# rc2014_8254.net
KiCad netlist of a schematic drawn in EAGLE
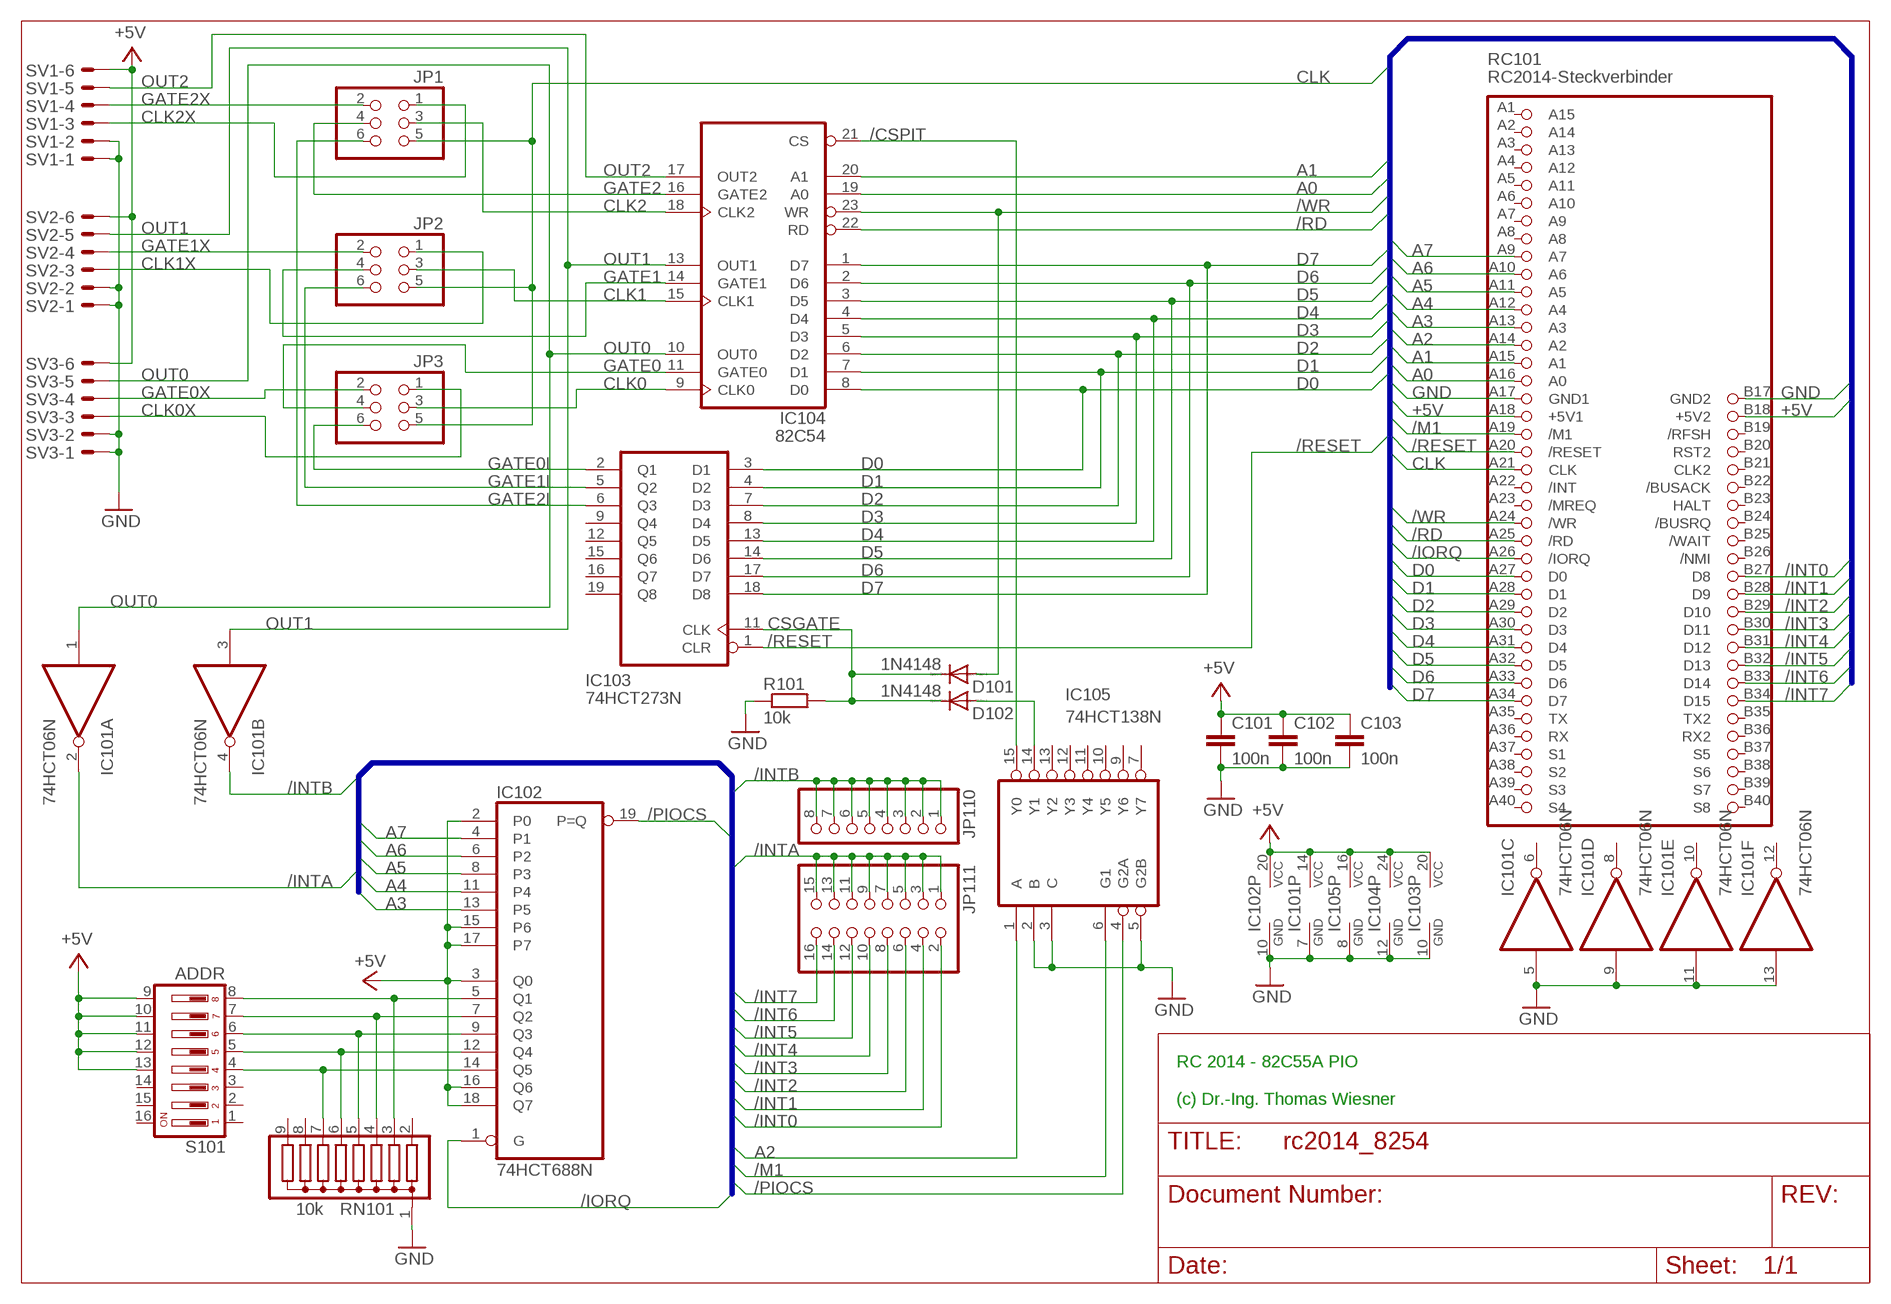
[diagram p0: schematic, sheet 1]

(export (version "E")
  (design (tool "Eeschema 10.0.6"))
  (components
    (comp (ref "C101")
      (value "100n")
      (footprint "eagle-import:C025-025X050")
      (libsource (lib "eagle-import") (part "C-EU025-025X050"))
    )
    (comp (ref "C102")
      (value "100n")
      (footprint "eagle-import:C025-025X050")
      (libsource (lib "eagle-import") (part "C-EU025-025X050"))
    )
    (comp (ref "C103")
      (value "100n")
      (footprint "eagle-import:C025-025X050")
      (libsource (lib "eagle-import") (part "C-EU025-025X050"))
    )
    (comp (ref "D101")
      (value "1N4148")
      (footprint "eagle-import:DO35-7")
      (libsource (lib "eagle-import") (part "1N4148DO35-7"))
    )
    (comp (ref "D102")
      (value "1N4148")
      (footprint "eagle-import:DO35-7")
      (libsource (lib "eagle-import") (part "1N4148DO35-7"))
    )
    (comp (ref "IC101")
      (value "74HCT06N")
      (footprint "eagle-import:DIL14")
      (libsource (lib "eagle-import") (part "7406NLS"))
    )
    (comp (ref "IC102")
      (value "74HCT688N")
      (footprint "eagle-import:DIL20")
      (libsource (lib "eagle-import") (part "74688NHCT"))
    )
    (comp (ref "IC103")
      (value "74HCT273N")
      (footprint "eagle-import:DIL20")
      (libsource (lib "eagle-import") (part "74273NHCT"))
    )
    (comp (ref "IC104")
      (value "82C54")
      (footprint "eagle-import:DIL24-6")
      (libsource (lib "eagle-import") (part "8253"))
    )
    (comp (ref "IC105")
      (value "74HCT138N")
      (footprint "eagle-import:DIL16")
      (libsource (lib "eagle-import") (part "74138NHCT"))
    )
    (comp (ref "JP1")
      (value "PINHD-2X3")
      (footprint "eagle-import:2X03")
      (libsource (lib "eagle-import") (part "PINHD-2X3"))
    )
    (comp (ref "JP2")
      (value "PINHD-2X3")
      (footprint "eagle-import:2X03")
      (libsource (lib "eagle-import") (part "PINHD-2X3"))
    )
    (comp (ref "JP3")
      (value "PINHD-2X3")
      (footprint "eagle-import:2X03")
      (libsource (lib "eagle-import") (part "PINHD-2X3"))
    )
    (comp (ref "JP110")
      (value "PINHD-1X8")
      (footprint "eagle-import:1X08")
      (libsource (lib "eagle-import") (part "PINHD-1X8"))
    )
    (comp (ref "JP111")
      (value "PINHD-2X8")
      (footprint "eagle-import:2X08")
      (libsource (lib "eagle-import") (part "PINHD-2X8"))
    )
    (comp (ref "R101")
      (value "10k")
      (footprint "eagle-import:0207_10")
      (libsource (lib "eagle-import") (part "R-EU_0207/10"))
    )
    (comp (ref "RC101")
      (value "RC2014-Steckverbinder")
      (footprint "eagle-import:RC2014-STECKER")
      (libsource (lib "eagle-import") (part "RC2014STECKER"))
    )
    (comp (ref "RN101")
      (value "10k")
      (footprint "eagle-import:SIL9")
      (libsource (lib "eagle-import") (part "G08R"))
    )
    (comp (ref "S101")
      (value "ADDR")
      (footprint "eagle-import:DS-08")
      (fields (field (name "MPN") "DS08"))
      (libsource (lib "eagle-import") (part "DS08"))
    )
    (comp (ref "SV1")
      (value "ML6LE")
      (footprint "eagle-import:ML6L")
      (libsource (lib "eagle-import") (part "ML6LE"))
    )
    (comp (ref "SV2")
      (value "ML6LE")
      (footprint "eagle-import:ML6L")
      (libsource (lib "eagle-import") (part "ML6LE"))
    )
    (comp (ref "SV3")
      (value "ML6LE")
      (footprint "eagle-import:ML6L")
      (libsource (lib "eagle-import") (part "ML6LE"))
    )
  )
  (nets
    (net (code "2") (name "+5V") (class "Default")
      (node (ref "C101") (pin "1") (pinfunction "1_1") (pintype "passive"))
      (node (ref "C102") (pin "1") (pinfunction "1_1") (pintype "passive"))
      (node (ref "C103") (pin "1") (pinfunction "1_1") (pintype "passive"))
      (node (ref "IC101") (pin "14") (pinfunction "VCC_14") (pintype "power_in"))
      (node (ref "IC102") (pin "15") (pinfunction "P6_15") (pintype "input"))
      (node (ref "IC102") (pin "16") (pinfunction "Q6_16") (pintype "input"))
      (node (ref "IC102") (pin "17") (pinfunction "P7_17") (pintype "input"))
      (node (ref "IC102") (pin "18") (pinfunction "Q7_18") (pintype "input"))
      (node (ref "IC102") (pin "2") (pinfunction "P0_2") (pintype "input"))
      (node (ref "IC102") (pin "20") (pinfunction "VCC_20") (pintype "power_in"))
      (node (ref "IC102") (pin "3") (pinfunction "Q0_3") (pintype "input"))
      (node (ref "IC103") (pin "20") (pinfunction "VCC_20") (pintype "power_in"))
      (node (ref "IC104") (pin "24") (pinfunction "VCC_24") (pintype "power_in"))
      (node (ref "IC105") (pin "16") (pinfunction "VCC_16") (pintype "power_in"))
      (node (ref "RC101") (pin "A18") (pinfunction "+5V1_A18") (pintype "passive"))
      (node (ref "RC101") (pin "B18") (pinfunction "+5V2_B18") (pintype "passive"))
      (node (ref "S101") (pin "10") (pinfunction "10_10") (pintype "passive"))
      (node (ref "S101") (pin "11") (pinfunction "11_11") (pintype "passive"))
      (node (ref "S101") (pin "12") (pinfunction "12_12") (pintype "passive"))
      (node (ref "S101") (pin "13") (pinfunction "13_13") (pintype "passive"))
      (node (ref "S101") (pin "9") (pinfunction "9_9") (pintype "passive"))
      (node (ref "SV1") (pin "6") (pinfunction "S_6") (pintype "passive"))
      (node (ref "SV2") (pin "6") (pinfunction "S_6") (pintype "passive"))
      (node (ref "SV3") (pin "6") (pinfunction "S_6") (pintype "passive"))
    )
    (net (code "4") (name "A0") (class "Default")
      (node (ref "IC104") (pin "19") (pinfunction "A0_19") (pintype "input"))
      (node (ref "RC101") (pin "A16") (pinfunction "A0_A16") (pintype "passive"))
    )
    (net (code "5") (name "A1") (class "Default")
      (node (ref "IC104") (pin "20") (pinfunction "A1_20") (pintype "input"))
      (node (ref "RC101") (pin "A15") (pinfunction "A1_A15") (pintype "passive"))
    )
    (net (code "6") (name "A2") (class "Default")
      (node (ref "IC105") (pin "1") (pinfunction "A_1") (pintype "input"))
      (node (ref "RC101") (pin "A14") (pinfunction "A2_A14") (pintype "passive"))
    )
    (net (code "7") (name "A3") (class "Default")
      (node (ref "IC102") (pin "13") (pinfunction "P5_13") (pintype "input"))
      (node (ref "RC101") (pin "A13") (pinfunction "A3_A13") (pintype "passive"))
    )
    (net (code "8") (name "A4") (class "Default")
      (node (ref "IC102") (pin "11") (pinfunction "P4_11") (pintype "input"))
      (node (ref "RC101") (pin "A12") (pinfunction "A4_A12") (pintype "passive"))
    )
    (net (code "9") (name "A5") (class "Default")
      (node (ref "IC102") (pin "8") (pinfunction "P3_8") (pintype "input"))
      (node (ref "RC101") (pin "A11") (pinfunction "A5_A11") (pintype "passive"))
    )
    (net (code "10") (name "A6") (class "Default")
      (node (ref "IC102") (pin "6") (pinfunction "P2_6") (pintype "input"))
      (node (ref "RC101") (pin "A10") (pinfunction "A6_A10") (pintype "passive"))
    )
    (net (code "11") (name "A7") (class "Default")
      (node (ref "IC102") (pin "4") (pinfunction "P1_4") (pintype "input"))
      (node (ref "RC101") (pin "A9") (pinfunction "A7_A9") (pintype "passive"))
    )
    (net (code "12") (name "CLK") (class "Default")
      (node (ref "JP1") (pin "5") (pinfunction "5_5") (pintype "passive"))
      (node (ref "JP2") (pin "5") (pinfunction "5_5") (pintype "passive"))
      (node (ref "JP3") (pin "5") (pinfunction "5_5") (pintype "passive"))
      (node (ref "RC101") (pin "A21") (pinfunction "CLK_A21") (pintype "passive"))
    )
    (net (code "13") (name "CLK0") (class "Default")
      (node (ref "IC104") (pin "9") (pinfunction "CLK0_9") (pintype "input"))
      (node (ref "JP3") (pin "3") (pinfunction "3_3") (pintype "passive"))
    )
    (net (code "14") (name "CLK0X") (class "Default")
      (node (ref "JP3") (pin "1") (pinfunction "1_1") (pintype "passive"))
      (node (ref "SV3") (pin "3") (pinfunction "S_3") (pintype "passive"))
    )
    (net (code "15") (name "CLK1") (class "Default")
      (node (ref "IC104") (pin "15") (pinfunction "CLK1_15") (pintype "input"))
      (node (ref "JP2") (pin "3") (pinfunction "3_3") (pintype "passive"))
    )
    (net (code "16") (name "CLK1X") (class "Default")
      (node (ref "JP2") (pin "1") (pinfunction "1_1") (pintype "passive"))
      (node (ref "SV2") (pin "3") (pinfunction "S_3") (pintype "passive"))
    )
    (net (code "17") (name "CLK2") (class "Default")
      (node (ref "IC104") (pin "18") (pinfunction "CLK2_18") (pintype "input"))
      (node (ref "JP1") (pin "3") (pinfunction "3_3") (pintype "passive"))
    )
    (net (code "18") (name "CLK2X") (class "Default")
      (node (ref "JP1") (pin "1") (pinfunction "1_1") (pintype "passive"))
      (node (ref "SV1") (pin "3") (pinfunction "S_3") (pintype "passive"))
    )
    (net (code "19") (name "CSGATE") (class "Default")
      (node (ref "D101") (pin "C") (pinfunction "C_C") (pintype "passive"))
      (node (ref "D102") (pin "C") (pinfunction "C_C") (pintype "passive"))
      (node (ref "IC103") (pin "11") (pinfunction "CLK_11") (pintype "input"))
      (node (ref "R101") (pin "2") (pinfunction "2_2") (pintype "passive"))
    )
    (net (code "20") (name "D0") (class "Default")
      (node (ref "IC103") (pin "3") (pinfunction "D1_3") (pintype "input"))
      (node (ref "IC104") (pin "8") (pinfunction "D0_8") (pintype "bidirectional"))
      (node (ref "RC101") (pin "A27") (pinfunction "D0_A27") (pintype "passive"))
    )
    (net (code "21") (name "D1") (class "Default")
      (node (ref "IC103") (pin "4") (pinfunction "D2_4") (pintype "input"))
      (node (ref "IC104") (pin "7") (pinfunction "D1_7") (pintype "bidirectional"))
      (node (ref "RC101") (pin "A28") (pinfunction "D1_A28") (pintype "passive"))
    )
    (net (code "22") (name "D2") (class "Default")
      (node (ref "IC103") (pin "7") (pinfunction "D3_7") (pintype "input"))
      (node (ref "IC104") (pin "6") (pinfunction "D2_6") (pintype "bidirectional"))
      (node (ref "RC101") (pin "A29") (pinfunction "D2_A29") (pintype "passive"))
    )
    (net (code "23") (name "D3") (class "Default")
      (node (ref "IC103") (pin "8") (pinfunction "D4_8") (pintype "input"))
      (node (ref "IC104") (pin "5") (pinfunction "D3_5") (pintype "bidirectional"))
      (node (ref "RC101") (pin "A30") (pinfunction "D3_A30") (pintype "passive"))
    )
    (net (code "24") (name "D4") (class "Default")
      (node (ref "IC103") (pin "13") (pinfunction "D5_13") (pintype "input"))
      (node (ref "IC104") (pin "4") (pinfunction "D4_4") (pintype "bidirectional"))
      (node (ref "RC101") (pin "A31") (pinfunction "D4_A31") (pintype "passive"))
    )
    (net (code "25") (name "D5") (class "Default")
      (node (ref "IC103") (pin "14") (pinfunction "D6_14") (pintype "input"))
      (node (ref "IC104") (pin "3") (pinfunction "D5_3") (pintype "bidirectional"))
      (node (ref "RC101") (pin "A32") (pinfunction "D5_A32") (pintype "passive"))
    )
    (net (code "26") (name "D6") (class "Default")
      (node (ref "IC103") (pin "17") (pinfunction "D7_17") (pintype "input"))
      (node (ref "IC104") (pin "2") (pinfunction "D6_2") (pintype "bidirectional"))
      (node (ref "RC101") (pin "A33") (pinfunction "D6_A33") (pintype "passive"))
    )
    (net (code "27") (name "D7") (class "Default")
      (node (ref "IC103") (pin "18") (pinfunction "D8_18") (pintype "input"))
      (node (ref "IC104") (pin "1") (pinfunction "D7_1") (pintype "bidirectional"))
      (node (ref "RC101") (pin "A34") (pinfunction "D7_A34") (pintype "passive"))
    )
    (net (code "28") (name "GATE0") (class "Default")
      (node (ref "IC104") (pin "11") (pinfunction "GATE0_11") (pintype "input"))
      (node (ref "JP3") (pin "4") (pinfunction "4_4") (pintype "passive"))
    )
    (net (code "29") (name "GATE0I") (class "Default")
      (node (ref "IC103") (pin "2") (pinfunction "Q1_2") (pintype "output"))
      (node (ref "JP3") (pin "6") (pinfunction "6_6") (pintype "passive"))
    )
    (net (code "30") (name "GATE0X") (class "Default")
      (node (ref "JP3") (pin "2") (pinfunction "2_2") (pintype "passive"))
      (node (ref "SV3") (pin "4") (pinfunction "S_4") (pintype "passive"))
    )
    (net (code "31") (name "GATE1") (class "Default")
      (node (ref "IC104") (pin "14") (pinfunction "GATE1_14") (pintype "input"))
      (node (ref "JP2") (pin "4") (pinfunction "4_4") (pintype "passive"))
    )
    (net (code "32") (name "GATE1I") (class "Default")
      (node (ref "IC103") (pin "5") (pinfunction "Q2_5") (pintype "output"))
      (node (ref "JP2") (pin "6") (pinfunction "6_6") (pintype "passive"))
    )
    (net (code "33") (name "GATE1X") (class "Default")
      (node (ref "JP2") (pin "2") (pinfunction "2_2") (pintype "passive"))
      (node (ref "SV2") (pin "4") (pinfunction "S_4") (pintype "passive"))
    )
    (net (code "34") (name "GATE2") (class "Default")
      (node (ref "IC104") (pin "16") (pinfunction "GATE2_16") (pintype "input"))
      (node (ref "JP1") (pin "4") (pinfunction "4_4") (pintype "passive"))
    )
    (net (code "35") (name "GATE2I") (class "Default")
      (node (ref "IC103") (pin "6") (pinfunction "Q3_6") (pintype "output"))
      (node (ref "JP1") (pin "6") (pinfunction "6_6") (pintype "passive"))
    )
    (net (code "36") (name "GATE2X") (class "Default")
      (node (ref "JP1") (pin "2") (pinfunction "2_2") (pintype "passive"))
      (node (ref "SV1") (pin "4") (pinfunction "S_4") (pintype "passive"))
    )
    (net (code "37") (name "GND") (class "Default")
      (node (ref "C101") (pin "2") (pinfunction "2_2") (pintype "passive"))
      (node (ref "C102") (pin "2") (pinfunction "2_2") (pintype "passive"))
      (node (ref "C103") (pin "2") (pinfunction "2_2") (pintype "passive"))
      (node (ref "IC101") (pin "11") (pinfunction "I_11") (pintype "input"))
      (node (ref "IC101") (pin "13") (pinfunction "I_13") (pintype "input"))
      (node (ref "IC101") (pin "5") (pinfunction "I_5") (pintype "input"))
      (node (ref "IC101") (pin "7") (pinfunction "GND_7") (pintype "power_in"))
      (node (ref "IC101") (pin "9") (pinfunction "I_9") (pintype "input"))
      (node (ref "IC102") (pin "10") (pinfunction "GND_10") (pintype "power_in"))
      (node (ref "IC103") (pin "10") (pinfunction "GND_10") (pintype "power_in"))
      (node (ref "IC104") (pin "12") (pinfunction "GND_12") (pintype "power_in"))
      (node (ref "IC105") (pin "2") (pinfunction "B_2") (pintype "input"))
      (node (ref "IC105") (pin "3") (pinfunction "C_3") (pintype "input"))
      (node (ref "IC105") (pin "5") (pinfunction "G2B_5") (pintype "input"))
      (node (ref "IC105") (pin "8") (pinfunction "GND_8") (pintype "power_in"))
      (node (ref "R101") (pin "1") (pinfunction "1_1") (pintype "passive"))
      (node (ref "RC101") (pin "A17") (pinfunction "GND1_A17") (pintype "passive"))
      (node (ref "RC101") (pin "B17") (pinfunction "GND2_B17") (pintype "passive"))
      (node (ref "RN101") (pin "1") (pinfunction "1_1") (pintype "passive"))
      (node (ref "SV1") (pin "1") (pinfunction "S_1") (pintype "passive"))
      (node (ref "SV1") (pin "2") (pinfunction "S_2") (pintype "passive"))
      (node (ref "SV2") (pin "1") (pinfunction "S_1") (pintype "passive"))
      (node (ref "SV2") (pin "2") (pinfunction "S_2") (pintype "passive"))
      (node (ref "SV3") (pin "1") (pinfunction "S_1") (pintype "passive"))
      (node (ref "SV3") (pin "2") (pinfunction "S_2") (pintype "passive"))
    )
    (net (code "38") (name "Net-(IC102A-Q1)") (class "Default")
      (node (ref "IC102") (pin "5") (pinfunction "Q1_5") (pintype "input"))
      (node (ref "RN101") (pin "3") (pinfunction "3_3") (pintype "passive"))
      (node (ref "S101") (pin "8") (pinfunction "8_8") (pintype "passive"))
    )
    (net (code "39") (name "Net-(IC102A-Q2)") (class "Default")
      (node (ref "IC102") (pin "7") (pinfunction "Q2_7") (pintype "input"))
      (node (ref "RN101") (pin "4") (pinfunction "4_4") (pintype "passive"))
      (node (ref "S101") (pin "7") (pinfunction "7_7") (pintype "passive"))
    )
    (net (code "40") (name "Net-(IC102A-Q3)") (class "Default")
      (node (ref "IC102") (pin "9") (pinfunction "Q3_9") (pintype "input"))
      (node (ref "RN101") (pin "5") (pinfunction "5_5") (pintype "passive"))
      (node (ref "S101") (pin "6") (pinfunction "6_6") (pintype "passive"))
    )
    (net (code "41") (name "Net-(IC102A-Q4)") (class "Default")
      (node (ref "IC102") (pin "12") (pinfunction "Q4_12") (pintype "input"))
      (node (ref "RN101") (pin "6") (pinfunction "6_6") (pintype "passive"))
      (node (ref "S101") (pin "5") (pinfunction "5_5") (pintype "passive"))
    )
    (net (code "42") (name "Net-(IC102A-Q5)") (class "Default")
      (node (ref "IC102") (pin "14") (pinfunction "Q5_14") (pintype "input"))
      (node (ref "RN101") (pin "7") (pinfunction "7_7") (pintype "passive"))
      (node (ref "S101") (pin "4") (pinfunction "4_4") (pintype "passive"))
    )
    (net (code "43") (name "Net-(IC105A-Y1)") (class "Default")
      (node (ref "D102") (pin "A") (pinfunction "A_A") (pintype "passive"))
      (node (ref "IC105") (pin "14") (pinfunction "Y1_14") (pintype "output"))
    )
    (net (code "44") (name "OUT0") (class "Default")
      (node (ref "IC101") (pin "1") (pinfunction "I_1") (pintype "input"))
      (node (ref "IC104") (pin "10") (pinfunction "OUT0_10") (pintype "output"))
      (node (ref "SV3") (pin "5") (pinfunction "S_5") (pintype "passive"))
    )
    (net (code "45") (name "OUT1") (class "Default")
      (node (ref "IC101") (pin "3") (pinfunction "I_3") (pintype "input"))
      (node (ref "IC104") (pin "13") (pinfunction "OUT1_13") (pintype "output"))
      (node (ref "SV2") (pin "5") (pinfunction "S_5") (pintype "passive"))
    )
    (net (code "46") (name "OUT2") (class "Default")
      (node (ref "IC104") (pin "17") (pinfunction "OUT2_17") (pintype "output"))
      (node (ref "SV1") (pin "5") (pinfunction "S_5") (pintype "passive"))
    )
    (net (code "47") (name "unconnected-(IC101C-O-Pad6)") (class "Default")
      (node (ref "IC101") (pin "6") (pinfunction "O_6") (pintype "open_collector"))
    )
    (net (code "48") (name "unconnected-(IC101D-O-Pad8)") (class "Default")
      (node (ref "IC101") (pin "8") (pinfunction "O_8") (pintype "open_collector"))
    )
    (net (code "49") (name "unconnected-(IC101E-O-Pad10)") (class "Default")
      (node (ref "IC101") (pin "10") (pinfunction "O_10") (pintype "open_collector"))
    )
    (net (code "50") (name "unconnected-(IC101F-O-Pad12)") (class "Default")
      (node (ref "IC101") (pin "12") (pinfunction "O_12") (pintype "open_collector"))
    )
    (net (code "51") (name "unconnected-(IC103A-Q4-Pad9)") (class "Default")
      (node (ref "IC103") (pin "9") (pinfunction "Q4_9") (pintype "output"))
    )
    (net (code "52") (name "unconnected-(IC103A-Q5-Pad12)") (class "Default")
      (node (ref "IC103") (pin "12") (pinfunction "Q5_12") (pintype "output"))
    )
    (net (code "53") (name "unconnected-(IC103A-Q6-Pad15)") (class "Default")
      (node (ref "IC103") (pin "15") (pinfunction "Q6_15") (pintype "output"))
    )
    (net (code "54") (name "unconnected-(IC103A-Q7-Pad16)") (class "Default")
      (node (ref "IC103") (pin "16") (pinfunction "Q7_16") (pintype "output"))
    )
    (net (code "55") (name "unconnected-(IC103A-Q8-Pad19)") (class "Default")
      (node (ref "IC103") (pin "19") (pinfunction "Q8_19") (pintype "output"))
    )
    (net (code "56") (name "unconnected-(IC105A-Y2-Pad13)") (class "Default")
      (node (ref "IC105") (pin "13") (pinfunction "Y2_13") (pintype "output"))
    )
    (net (code "57") (name "unconnected-(IC105A-Y3-Pad12)") (class "Default")
      (node (ref "IC105") (pin "12") (pinfunction "Y3_12") (pintype "output"))
    )
    (net (code "58") (name "unconnected-(IC105A-Y4-Pad11)") (class "Default")
      (node (ref "IC105") (pin "11") (pinfunction "Y4_11") (pintype "output"))
    )
    (net (code "59") (name "unconnected-(IC105A-Y5-Pad10)") (class "Default")
      (node (ref "IC105") (pin "10") (pinfunction "Y5_10") (pintype "output"))
    )
    (net (code "60") (name "unconnected-(IC105A-Y6-Pad9)") (class "Default")
      (node (ref "IC105") (pin "9") (pinfunction "Y6_9") (pintype "output"))
    )
    (net (code "61") (name "unconnected-(IC105A-Y7-Pad7)") (class "Default")
      (node (ref "IC105") (pin "7") (pinfunction "Y7_7") (pintype "output"))
    )
    (net (code "62") (name "unconnected-(RC101-A9-PadA7)") (class "Default")
      (node (ref "RC101") (pin "A7") (pinfunction "A9_A7") (pintype "passive"))
    )
    (net (code "63") (name "unconnected-(RC101-A10-PadA6)") (class "Default")
      (node (ref "RC101") (pin "A6") (pinfunction "A10_A6") (pintype "passive"))
    )
    (net (code "64") (name "unconnected-(RC101-A11-PadA5)") (class "Default")
      (node (ref "RC101") (pin "A5") (pinfunction "A11_A5") (pintype "passive"))
    )
    (net (code "65") (name "unconnected-(RC101-A12-PadA4)") (class "Default")
      (node (ref "RC101") (pin "A4") (pinfunction "A12_A4") (pintype "passive"))
    )
    (net (code "66") (name "unconnected-(RC101-A13-PadA3)") (class "Default")
      (node (ref "RC101") (pin "A3") (pinfunction "A13_A3") (pintype "passive"))
    )
    (net (code "67") (name "unconnected-(RC101-A14-PadA2)") (class "Default")
      (node (ref "RC101") (pin "A2") (pinfunction "A14_A2") (pintype "passive"))
    )
    (net (code "68") (name "unconnected-(RC101-A15-PadA1)") (class "Default")
      (node (ref "RC101") (pin "A1") (pinfunction "A15_A1") (pintype "passive"))
    )
    (net (code "69") (name "unconnected-(RC101-CLK2-PadB21)") (class "Default")
      (node (ref "RC101") (pin "B21") (pinfunction "CLK2_B21") (pintype "passive"))
    )
    (net (code "70") (name "unconnected-(RC101-HALT-PadB23)") (class "Default")
      (node (ref "RC101") (pin "B23") (pinfunction "HALT_B23") (pintype "passive"))
    )
    (net (code "71") (name "unconnected-(RC101-PadA8)") (class "Default")
      (node (ref "RC101") (pin "A8") (pinfunction "A8_A8") (pintype "passive"))
    )
    (net (code "72") (name "unconnected-(RC101-RST2-PadB20)") (class "Default")
      (node (ref "RC101") (pin "B20") (pinfunction "RST2_B20") (pintype "passive"))
    )
    (net (code "73") (name "unconnected-(RC101-RX-PadA36)") (class "Default")
      (node (ref "RC101") (pin "A36") (pinfunction "RX_A36") (pintype "passive"))
    )
    (net (code "74") (name "unconnected-(RC101-RX2-PadB36)") (class "Default")
      (node (ref "RC101") (pin "B36") (pinfunction "RX2_B36") (pintype "passive"))
    )
    (net (code "75") (name "unconnected-(RC101-S1-PadA37)") (class "Default")
      (node (ref "RC101") (pin "A37") (pinfunction "S1_A37") (pintype "passive"))
    )
    (net (code "76") (name "unconnected-(RC101-S2-PadA38)") (class "Default")
      (node (ref "RC101") (pin "A38") (pinfunction "S2_A38") (pintype "passive"))
    )
    (net (code "77") (name "unconnected-(RC101-S3-PadA39)") (class "Default")
      (node (ref "RC101") (pin "A39") (pinfunction "S3_A39") (pintype "passive"))
    )
    (net (code "78") (name "unconnected-(RC101-S4-PadA40)") (class "Default")
      (node (ref "RC101") (pin "A40") (pinfunction "S4_A40") (pintype "passive"))
    )
    (net (code "79") (name "unconnected-(RC101-S5-PadB37)") (class "Default")
      (node (ref "RC101") (pin "B37") (pinfunction "S5_B37") (pintype "passive"))
    )
    (net (code "80") (name "unconnected-(RC101-S6-PadB38)") (class "Default")
      (node (ref "RC101") (pin "B38") (pinfunction "S6_B38") (pintype "passive"))
    )
    (net (code "81") (name "unconnected-(RC101-S7-PadB39)") (class "Default")
      (node (ref "RC101") (pin "B39") (pinfunction "S7_B39") (pintype "passive"))
    )
    (net (code "82") (name "unconnected-(RC101-S8-PadB40)") (class "Default")
      (node (ref "RC101") (pin "B40") (pinfunction "S8_B40") (pintype "passive"))
    )
    (net (code "83") (name "unconnected-(RC101-TX-PadA35)") (class "Default")
      (node (ref "RC101") (pin "A35") (pinfunction "TX_A35") (pintype "passive"))
    )
    (net (code "84") (name "unconnected-(RC101-TX2-PadB35)") (class "Default")
      (node (ref "RC101") (pin "B35") (pinfunction "TX2_B35") (pintype "passive"))
    )
    (net (code "85") (name "unconnected-(RC101-{slash}BUSACK-PadB22)") (class "Default")
      (node (ref "RC101") (pin "B22") (pinfunction "/BUSACK_B22") (pintype "passive"))
    )
    (net (code "86") (name "unconnected-(RC101-{slash}BUSRQ-PadB24)") (class "Default")
      (node (ref "RC101") (pin "B24") (pinfunction "/BUSRQ_B24") (pintype "passive"))
    )
    (net (code "87") (name "unconnected-(RC101-{slash}INT-PadA22)") (class "Default")
      (node (ref "RC101") (pin "A22") (pinfunction "/INT_A22") (pintype "passive"))
    )
    (net (code "88") (name "unconnected-(RC101-{slash}MREQ-PadA23)") (class "Default")
      (node (ref "RC101") (pin "A23") (pinfunction "/MREQ_A23") (pintype "passive"))
    )
    (net (code "89") (name "unconnected-(RC101-{slash}NMI-PadB26)") (class "Default")
      (node (ref "RC101") (pin "B26") (pinfunction "/NMI_B26") (pintype "passive"))
    )
    (net (code "90") (name "unconnected-(RC101-{slash}RFSH-PadB19)") (class "Default")
      (node (ref "RC101") (pin "B19") (pinfunction "/RFSH_B19") (pintype "passive"))
    )
    (net (code "91") (name "unconnected-(RC101-{slash}WAIT-PadB25)") (class "Default")
      (node (ref "RC101") (pin "B25") (pinfunction "/WAIT_B25") (pintype "passive"))
    )
    (net (code "92") (name "unconnected-(RN101-Pad2)") (class "Default")
      (node (ref "RN101") (pin "2") (pinfunction "2_2") (pintype "passive"))
    )
    (net (code "93") (name "unconnected-(RN101-Pad8)") (class "Default")
      (node (ref "RN101") (pin "8") (pinfunction "8_8") (pintype "passive"))
    )
    (net (code "94") (name "unconnected-(RN101-Pad9)") (class "Default")
      (node (ref "RN101") (pin "9") (pinfunction "9_9") (pintype "passive"))
    )
    (net (code "95") (name "unconnected-(S101-Pad1)") (class "Default")
      (node (ref "S101") (pin "1") (pinfunction "1_1") (pintype "passive"))
    )
    (net (code "96") (name "unconnected-(S101-Pad2)") (class "Default")
      (node (ref "S101") (pin "2") (pinfunction "2_2") (pintype "passive"))
    )
    (net (code "97") (name "unconnected-(S101-Pad3)") (class "Default")
      (node (ref "S101") (pin "3") (pinfunction "3_3") (pintype "passive"))
    )
    (net (code "98") (name "unconnected-(S101-Pad14)") (class "Default")
      (node (ref "S101") (pin "14") (pinfunction "14_14") (pintype "passive"))
    )
    (net (code "99") (name "unconnected-(S101-Pad15)") (class "Default")
      (node (ref "S101") (pin "15") (pinfunction "15_15") (pintype "passive"))
    )
    (net (code "100") (name "unconnected-(S101-Pad16)") (class "Default")
      (node (ref "S101") (pin "16") (pinfunction "16_16") (pintype "passive"))
    )
    (net (code "101") (name "{slash}CSPIT") (class "Default")
      (node (ref "IC104") (pin "21") (pinfunction "CS_21") (pintype "input"))
      (node (ref "IC105") (pin "15") (pinfunction "Y0_15") (pintype "output"))
    )
    (net (code "102") (name "{slash}INT0") (class "Default")
      (node (ref "JP111") (pin "2") (pinfunction "2_2") (pintype "passive"))
      (node (ref "RC101") (pin "B27") (pinfunction "D8_B27") (pintype "passive"))
    )
    (net (code "103") (name "{slash}INT1") (class "Default")
      (node (ref "JP111") (pin "4") (pinfunction "4_4") (pintype "passive"))
      (node (ref "RC101") (pin "B28") (pinfunction "D9_B28") (pintype "passive"))
    )
    (net (code "104") (name "{slash}INT2") (class "Default")
      (node (ref "JP111") (pin "6") (pinfunction "6_6") (pintype "passive"))
      (node (ref "RC101") (pin "B29") (pinfunction "D10_B29") (pintype "passive"))
    )
    (net (code "105") (name "{slash}INT3") (class "Default")
      (node (ref "JP111") (pin "8") (pinfunction "8_8") (pintype "passive"))
      (node (ref "RC101") (pin "B30") (pinfunction "D11_B30") (pintype "passive"))
    )
    (net (code "106") (name "{slash}INT4") (class "Default")
      (node (ref "JP111") (pin "10") (pinfunction "10_10") (pintype "passive"))
      (node (ref "RC101") (pin "B31") (pinfunction "D12_B31") (pintype "passive"))
    )
    (net (code "107") (name "{slash}INT5") (class "Default")
      (node (ref "JP111") (pin "12") (pinfunction "12_12") (pintype "passive"))
      (node (ref "RC101") (pin "B32") (pinfunction "D13_B32") (pintype "passive"))
    )
    (net (code "108") (name "{slash}INT6") (class "Default")
      (node (ref "JP111") (pin "14") (pinfunction "14_14") (pintype "passive"))
      (node (ref "RC101") (pin "B33") (pinfunction "D14_B33") (pintype "passive"))
    )
    (net (code "109") (name "{slash}INT7") (class "Default")
      (node (ref "JP111") (pin "16") (pinfunction "16_16") (pintype "passive"))
      (node (ref "RC101") (pin "B34") (pinfunction "D15_B34") (pintype "passive"))
    )
    (net (code "110") (name "{slash}INTA") (class "Default")
      (node (ref "IC101") (pin "2") (pinfunction "O_2") (pintype "open_collector"))
      (node (ref "JP111") (pin "1") (pinfunction "1_1") (pintype "passive"))
      (node (ref "JP111") (pin "11") (pinfunction "11_11") (pintype "passive"))
      (node (ref "JP111") (pin "13") (pinfunction "13_13") (pintype "passive"))
      (node (ref "JP111") (pin "15") (pinfunction "15_15") (pintype "passive"))
      (node (ref "JP111") (pin "3") (pinfunction "3_3") (pintype "passive"))
      (node (ref "JP111") (pin "5") (pinfunction "5_5") (pintype "passive"))
      (node (ref "JP111") (pin "7") (pinfunction "7_7") (pintype "passive"))
      (node (ref "JP111") (pin "9") (pinfunction "9_9") (pintype "passive"))
    )
    (net (code "111") (name "{slash}INTB") (class "Default")
      (node (ref "IC101") (pin "4") (pinfunction "O_4") (pintype "open_collector"))
      (node (ref "JP110") (pin "1") (pinfunction "1_1") (pintype "passive"))
      (node (ref "JP110") (pin "2") (pinfunction "2_2") (pintype "passive"))
      (node (ref "JP110") (pin "3") (pinfunction "3_3") (pintype "passive"))
      (node (ref "JP110") (pin "4") (pinfunction "4_4") (pintype "passive"))
      (node (ref "JP110") (pin "5") (pinfunction "5_5") (pintype "passive"))
      (node (ref "JP110") (pin "6") (pinfunction "6_6") (pintype "passive"))
      (node (ref "JP110") (pin "7") (pinfunction "7_7") (pintype "passive"))
      (node (ref "JP110") (pin "8") (pinfunction "8_8") (pintype "passive"))
    )
    (net (code "112") (name "{slash}IORQ") (class "Default")
      (node (ref "IC102") (pin "1") (pinfunction "G_1") (pintype "input"))
      (node (ref "RC101") (pin "A26") (pinfunction "/IORQ_A26") (pintype "passive"))
    )
    (net (code "113") (name "{slash}M1") (class "Default")
      (node (ref "IC105") (pin "6") (pinfunction "G1_6") (pintype "input"))
      (node (ref "RC101") (pin "A19") (pinfunction "/M1_A19") (pintype "passive"))
    )
    (net (code "114") (name "{slash}PIOCS") (class "Default")
      (node (ref "IC102") (pin "19") (pinfunction "P=Q_19") (pintype "output"))
      (node (ref "IC105") (pin "4") (pinfunction "G2A_4") (pintype "input"))
    )
    (net (code "115") (name "{slash}RD") (class "Default")
      (node (ref "IC104") (pin "22") (pinfunction "RD_22") (pintype "input"))
      (node (ref "RC101") (pin "A25") (pinfunction "/RD_A25") (pintype "passive"))
    )
    (net (code "116") (name "{slash}RESET") (class "Default")
      (node (ref "IC103") (pin "1") (pinfunction "CLR_1") (pintype "input"))
      (node (ref "RC101") (pin "A20") (pinfunction "/RESET_A20") (pintype "passive"))
    )
    (net (code "117") (name "{slash}WR") (class "Default")
      (node (ref "D101") (pin "A") (pinfunction "A_A") (pintype "passive"))
      (node (ref "IC104") (pin "23") (pinfunction "WR_23") (pintype "input"))
      (node (ref "RC101") (pin "A24") (pinfunction "/WR_A24") (pintype "passive"))
    )
  )
)
